# e22-breakout.net
KiCad netlist of a schematic drawn in EAGLE
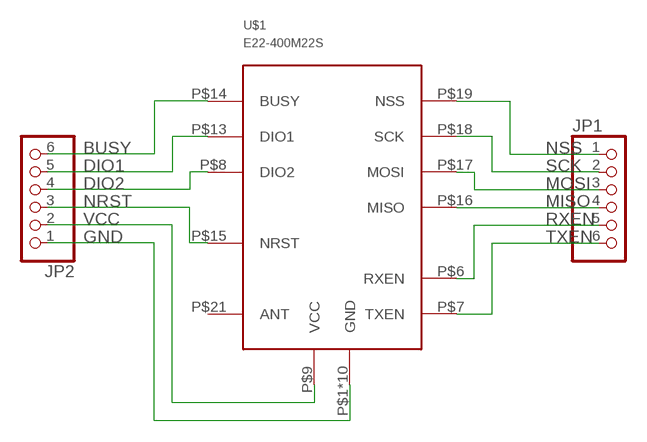
[diagram p0: schematic, sheet 1]

(export (version "E")
  (design (tool "Eeschema 10.0.6"))
  (components
    (comp (ref "JP1")
      (value "PINHD-1X6")
      (footprint "eagle-import:1X06")
      (libsource (lib "eagle-import") (part "PINHD-1X6"))
    )
    (comp (ref "JP2")
      (value "PINHD-1X6")
      (footprint "eagle-import:1X06")
      (libsource (lib "eagle-import") (part "PINHD-1X6"))
    )
    (comp (ref "U$1")
      (value "E22-400M22S")
      (footprint "eagle-import:E22-400M22S")
      (libsource (lib "eagle-import") (part "E22-400M22S"))
    )
  )
  (nets
    (net (code "1") (name "/BUSY") (class "Default")
      (node (ref "JP2") (pin "6") (pinfunction "6_6") (pintype "passive"))
      (node (ref "U$1") (pin "P$14") (pinfunction "BUSY_P$14") (pintype "output"))
    )
    (net (code "2") (name "/DIO1") (class "Default")
      (node (ref "JP2") (pin "5") (pinfunction "5_5") (pintype "passive"))
      (node (ref "U$1") (pin "P$13") (pinfunction "DIO1_P$13") (pintype "bidirectional"))
    )
    (net (code "3") (name "/DIO2") (class "Default")
      (node (ref "JP2") (pin "4") (pinfunction "4_4") (pintype "passive"))
      (node (ref "U$1") (pin "P$8") (pinfunction "DIO2_P$8") (pintype "bidirectional"))
    )
    (net (code "4") (name "/GND") (class "Default")
      (node (ref "JP2") (pin "1") (pinfunction "1_1") (pintype "passive"))
      (node (ref "U$1") (pin "P$1") (pinfunction "GND_P$1") (pintype "power_in"))
      (node (ref "U$1") (pin "P$10") (pinfunction "GND_P$10") (pintype "power_in"))
      (node (ref "U$1") (pin "P$11") (pinfunction "GND_P$11") (pintype "power_in"))
      (node (ref "U$1") (pin "P$12") (pinfunction "GND_P$12") (pintype "power_in"))
      (node (ref "U$1") (pin "P$2") (pinfunction "GND_P$2") (pintype "power_in"))
      (node (ref "U$1") (pin "P$20") (pinfunction "GND_P$20") (pintype "power_in"))
      (node (ref "U$1") (pin "P$22") (pinfunction "GND_P$22") (pintype "power_in"))
      (node (ref "U$1") (pin "P$3") (pinfunction "GND_P$3") (pintype "power_in"))
      (node (ref "U$1") (pin "P$4") (pinfunction "GND_P$4") (pintype "power_in"))
      (node (ref "U$1") (pin "P$5") (pinfunction "GND_P$5") (pintype "power_in"))
    )
    (net (code "5") (name "/MISO") (class "Default")
      (node (ref "JP1") (pin "4") (pinfunction "4_4") (pintype "passive"))
      (node (ref "U$1") (pin "P$16") (pinfunction "MISO_P$16") (pintype "output"))
    )
    (net (code "6") (name "/MOSI") (class "Default")
      (node (ref "JP1") (pin "3") (pinfunction "3_3") (pintype "passive"))
      (node (ref "U$1") (pin "P$17") (pinfunction "MOSI_P$17") (pintype "input"))
    )
    (net (code "7") (name "/NRST") (class "Default")
      (node (ref "JP2") (pin "3") (pinfunction "3_3") (pintype "passive"))
      (node (ref "U$1") (pin "P$15") (pinfunction "NRST_P$15") (pintype "input"))
    )
    (net (code "8") (name "/NSS") (class "Default")
      (node (ref "JP1") (pin "1") (pinfunction "1_1") (pintype "passive"))
      (node (ref "U$1") (pin "P$19") (pinfunction "NSS_P$19") (pintype "input"))
    )
    (net (code "9") (name "/RXEN") (class "Default")
      (node (ref "JP1") (pin "5") (pinfunction "5_5") (pintype "passive"))
      (node (ref "U$1") (pin "P$6") (pinfunction "RXEN_P$6") (pintype "input"))
    )
    (net (code "10") (name "/SCK") (class "Default")
      (node (ref "JP1") (pin "2") (pinfunction "2_2") (pintype "passive"))
      (node (ref "U$1") (pin "P$18") (pinfunction "SCK_P$18") (pintype "input"))
    )
    (net (code "11") (name "/TXEN") (class "Default")
      (node (ref "JP1") (pin "6") (pinfunction "6_6") (pintype "passive"))
      (node (ref "U$1") (pin "P$7") (pinfunction "TXEN_P$7") (pintype "input"))
    )
    (net (code "12") (name "/VCC") (class "Default")
      (node (ref "JP2") (pin "2") (pinfunction "2_2") (pintype "passive"))
      (node (ref "U$1") (pin "P$9") (pinfunction "VCC_P$9") (pintype "power_in"))
    )
    (net (code "13") (name "unconnected-(U$1-ANT-PadP$21)") (class "Default")
      (node (ref "U$1") (pin "P$21") (pinfunction "ANT_P$21") (pintype "output"))
    )
  )
)
